# IndoorStation_PCB_M1.net
KiCad netlist of a schematic drawn in EAGLE
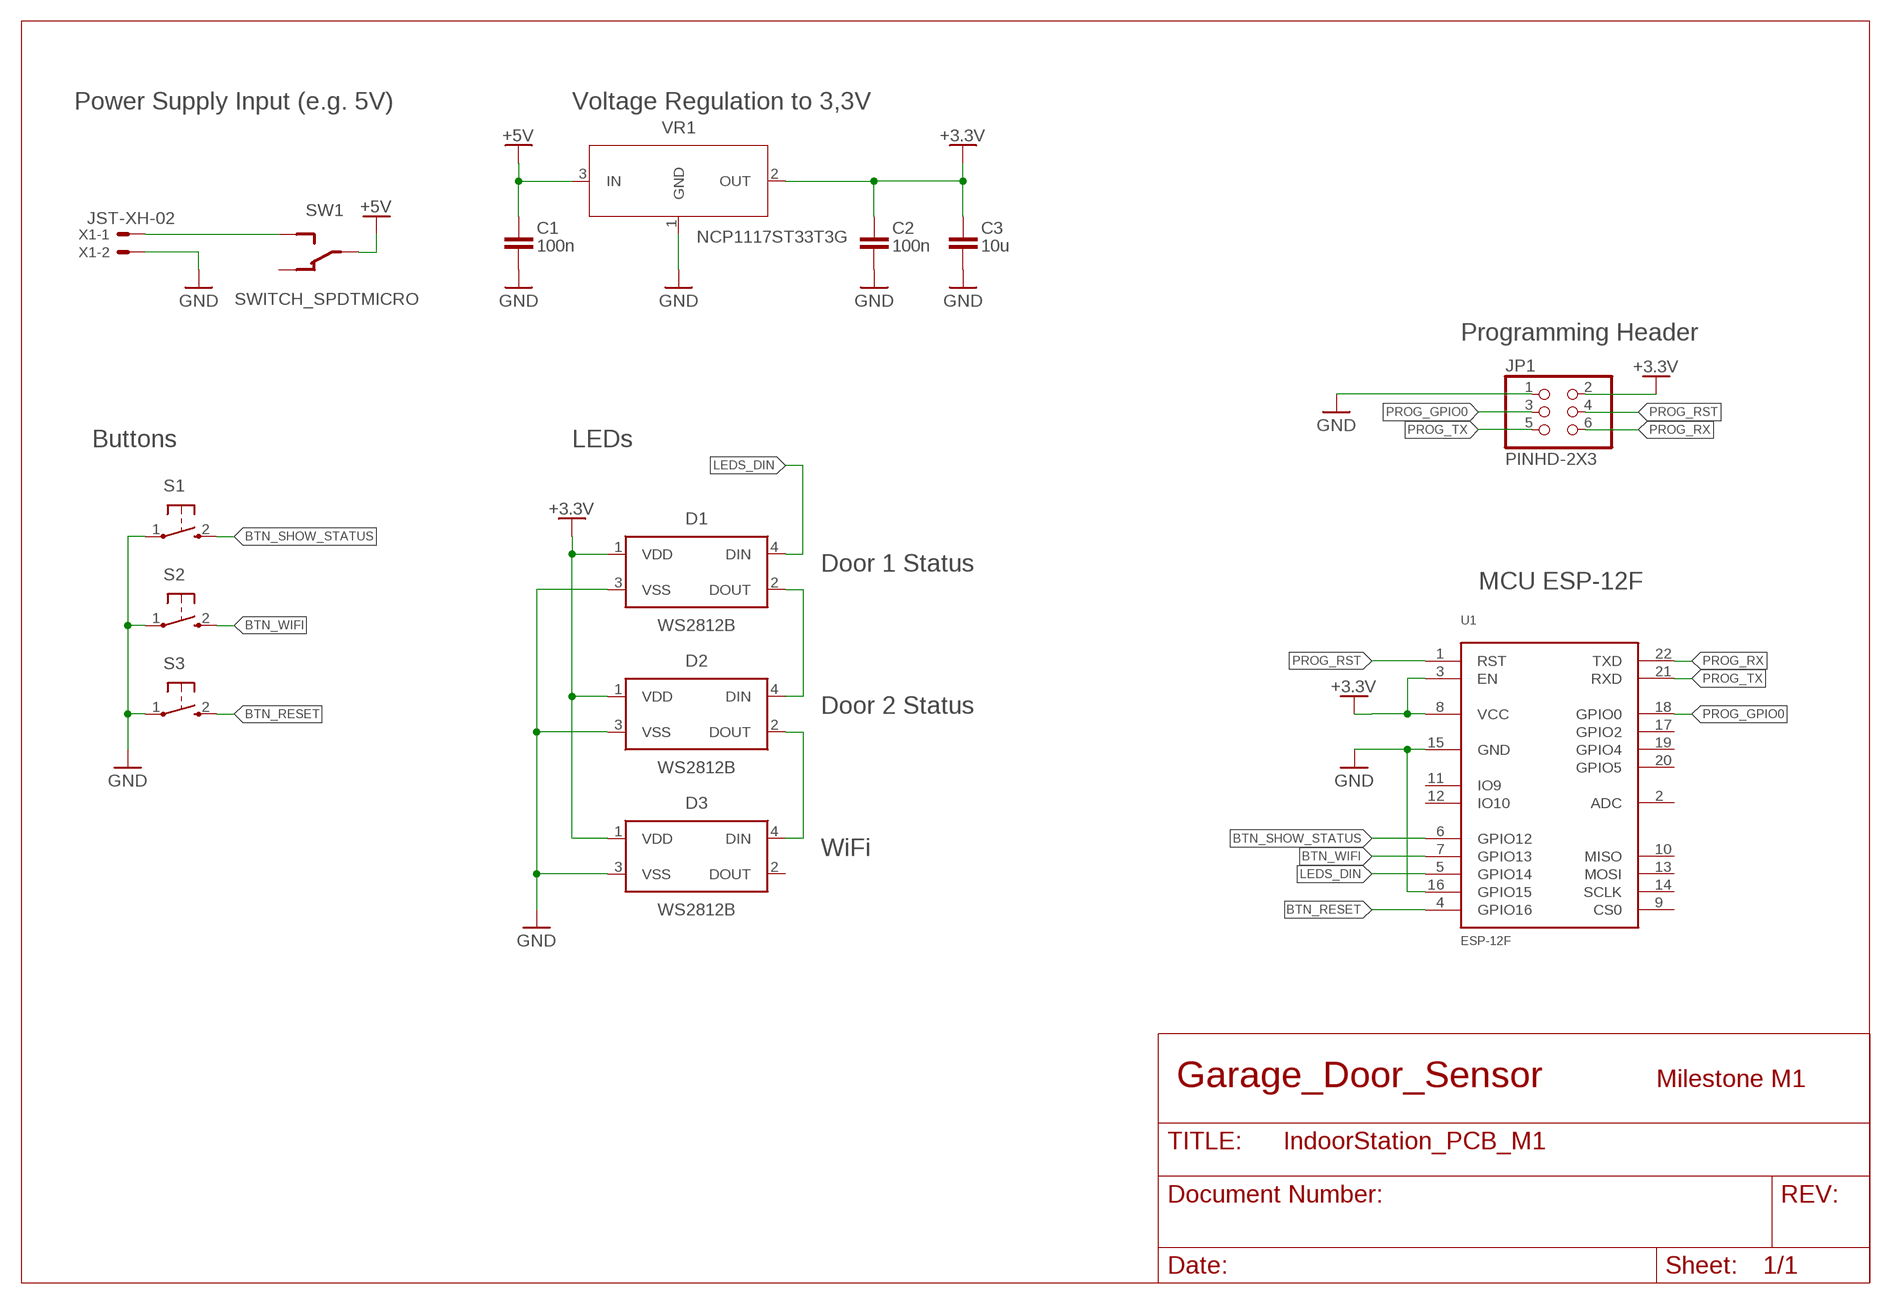
[diagram p0: schematic, sheet 1]

(export (version "E")
  (design (tool "Eeschema 10.0.6"))
  (components
    (comp (ref "C1")
      (value "100n")
      (footprint "eagle-import:CAPC2012X110")
      (libsource (lib "eagle-import") (part "CCHIP-0805(2012-METRIC)_"))
    )
    (comp (ref "C2")
      (value "100n")
      (footprint "eagle-import:CAPC2012X110")
      (libsource (lib "eagle-import") (part "CCHIP-0805(2012-METRIC)_"))
    )
    (comp (ref "C3")
      (value "10u")
      (footprint "eagle-import:CAPC2012X110")
      (libsource (lib "eagle-import") (part "CCHIP-0805(2012-METRIC)_"))
    )
    (comp (ref "D1")
      (value "WS2812B")
      (footprint "eagle-import:WS2812B")
      (fields (field (name "MANUFACTURER") "Worldsemi"))
      (libsource (lib "eagle-import") (part "WS2812B"))
    )
    (comp (ref "D2")
      (value "WS2812B")
      (footprint "eagle-import:WS2812B")
      (fields (field (name "MANUFACTURER") "Worldsemi"))
      (libsource (lib "eagle-import") (part "WS2812B"))
    )
    (comp (ref "D3")
      (value "WS2812B")
      (footprint "eagle-import:WS2812B")
      (fields (field (name "MANUFACTURER") "Worldsemi"))
      (libsource (lib "eagle-import") (part "WS2812B"))
    )
    (comp (ref "JP1")
      (value "PINHD-2X3")
      (footprint "eagle-import:2X03")
      (fields (field (name "MANUFACTURER") "Generic"))
      (libsource (lib "eagle-import") (part "PINHD-2X3"))
    )
    (comp (ref "S1")
      (value "KURZHUBTASTER")
      (footprint "eagle-import:B3F-10XX")
      (libsource (lib "eagle-import") (part "KURZHUBTASTER"))
    )
    (comp (ref "S2")
      (value "KURZHUBTASTER")
      (footprint "eagle-import:B3F-10XX")
      (libsource (lib "eagle-import") (part "KURZHUBTASTER"))
    )
    (comp (ref "S3")
      (value "KURZHUBTASTER")
      (footprint "eagle-import:B3F-10XX")
      (libsource (lib "eagle-import") (part "KURZHUBTASTER"))
    )
    (comp (ref "SW1")
      (value "SWITCH_SPDTMICRO")
      (footprint "eagle-import:MICROSWITCH_SPDT")
      (libsource (lib "eagle-import") (part "SWITCH_SPDTMICRO"))
    )
    (comp (ref "U1")
      (value "ESP-12F")
      (footprint "eagle-import:ESP-12F")
      (fields (field (name "MF") "AI-Thinker"))
      (libsource (lib "eagle-import") (part "ESP-12F"))
    )
    (comp (ref "VR1")
      (value "NCP1117ST33T3G")
      (footprint "eagle-import:SOT230P700X170-4")
      (fields (field (name "MANUFACTURER") "ON Semiconductor"))
      (libsource (lib "eagle-import") (part "NCP1117ST33T3GSOT-223"))
    )
    (comp (ref "X1")
      (value "JST-XH-02")
      (footprint "eagle-import:JST-XH-02-EDGE")
      (libsource (lib "eagle-import") (part "JST-XH-02-PIN-EDGE"))
    )
  )
  (nets
    (net (code "1") (name "+3.3V") (class "Default")
      (node (ref "C2") (pin "1") (pinfunction "1_1") (pintype "passive"))
      (node (ref "C3") (pin "1") (pinfunction "1_1") (pintype "passive"))
      (node (ref "D1") (pin "1") (pinfunction "VDD_1") (pintype "power_in"))
      (node (ref "D2") (pin "1") (pinfunction "VDD_1") (pintype "power_in"))
      (node (ref "D3") (pin "1") (pinfunction "VDD_1") (pintype "power_in"))
      (node (ref "JP1") (pin "2") (pinfunction "2_2") (pintype "passive"))
      (node (ref "U1") (pin "3") (pinfunction "EN_3") (pintype "bidirectional"))
      (node (ref "U1") (pin "8") (pinfunction "VCC_8") (pintype "bidirectional"))
      (node (ref "VR1") (pin "2") (pinfunction "OUT_2") (pintype "output"))
    )
    (net (code "2") (name "+5V") (class "Default")
      (node (ref "C1") (pin "1") (pinfunction "1_1") (pintype "passive"))
      (node (ref "SW1") (pin "P$2") (pinfunction "P$2_P$2") (pintype "passive"))
      (node (ref "VR1") (pin "3") (pinfunction "IN_3") (pintype "input"))
    )
    (net (code "3") (name "BTN_RESET") (class "Default")
      (node (ref "S3") (pin "2") (pinfunction "S_2") (pintype "passive"))
      (node (ref "U1") (pin "4") (pinfunction "GPIO16_4") (pintype "bidirectional"))
    )
    (net (code "4") (name "BTN_SHOW_STATUS") (class "Default")
      (node (ref "S1") (pin "2") (pinfunction "S_2") (pintype "passive"))
      (node (ref "U1") (pin "6") (pinfunction "GPIO12_6") (pintype "bidirectional"))
    )
    (net (code "5") (name "BTN_WIFI") (class "Default")
      (node (ref "S2") (pin "2") (pinfunction "S_2") (pintype "passive"))
      (node (ref "U1") (pin "7") (pinfunction "GPIO13_7") (pintype "bidirectional"))
    )
    (net (code "6") (name "GND") (class "Default")
      (node (ref "C1") (pin "2") (pinfunction "2_2") (pintype "passive"))
      (node (ref "C2") (pin "2") (pinfunction "2_2") (pintype "passive"))
      (node (ref "C3") (pin "2") (pinfunction "2_2") (pintype "passive"))
      (node (ref "D1") (pin "3") (pinfunction "VSS_3") (pintype "power_in"))
      (node (ref "D2") (pin "3") (pinfunction "VSS_3") (pintype "power_in"))
      (node (ref "D3") (pin "3") (pinfunction "VSS_3") (pintype "power_in"))
      (node (ref "JP1") (pin "1") (pinfunction "1_1") (pintype "passive"))
      (node (ref "S1") (pin "1") (pinfunction "P_1") (pintype "passive"))
      (node (ref "S2") (pin "1") (pinfunction "P_1") (pintype "passive"))
      (node (ref "S3") (pin "1") (pinfunction "P_1") (pintype "passive"))
      (node (ref "U1") (pin "15") (pinfunction "GND_15") (pintype "bidirectional"))
      (node (ref "U1") (pin "16") (pinfunction "GPIO15_16") (pintype "bidirectional"))
      (node (ref "VR1") (pin "1") (pinfunction "GND_1") (pintype "passive"))
      (node (ref "X1") (pin "P$2") (pinfunction "S_P$2") (pintype "passive"))
    )
    (net (code "7") (name "LEDS_DIN") (class "Default")
      (node (ref "D1") (pin "4") (pinfunction "DIN_4") (pintype "input"))
      (node (ref "U1") (pin "5") (pinfunction "GPIO14_5") (pintype "bidirectional"))
    )
    (net (code "8") (name "Net-(D1-DOUT)") (class "Default")
      (node (ref "D1") (pin "2") (pinfunction "DOUT_2") (pintype "output"))
      (node (ref "D2") (pin "4") (pinfunction "DIN_4") (pintype "input"))
    )
    (net (code "9") (name "Net-(D2-DOUT)") (class "Default")
      (node (ref "D2") (pin "2") (pinfunction "DOUT_2") (pintype "output"))
      (node (ref "D3") (pin "4") (pinfunction "DIN_4") (pintype "input"))
    )
    (net (code "10") (name "Net-(X1A-S)") (class "Default")
      (node (ref "SW1") (pin "P$1") (pinfunction "P$1_P$1") (pintype "passive"))
      (node (ref "X1") (pin "P$1") (pinfunction "S_P$1") (pintype "passive"))
    )
    (net (code "11") (name "PROG_GPIO0") (class "Default")
      (node (ref "JP1") (pin "3") (pinfunction "3_3") (pintype "passive"))
      (node (ref "U1") (pin "18") (pinfunction "GPIO0_18") (pintype "bidirectional"))
    )
    (net (code "12") (name "PROG_RST") (class "Default")
      (node (ref "JP1") (pin "4") (pinfunction "4_4") (pintype "passive"))
      (node (ref "U1") (pin "1") (pinfunction "RST_1") (pintype "bidirectional"))
    )
    (net (code "13") (name "PROG_RX") (class "Default")
      (node (ref "JP1") (pin "6") (pinfunction "6_6") (pintype "passive"))
      (node (ref "U1") (pin "22") (pinfunction "TXD_22") (pintype "bidirectional"))
    )
    (net (code "14") (name "PROG_TX") (class "Default")
      (node (ref "JP1") (pin "5") (pinfunction "5_5") (pintype "passive"))
      (node (ref "U1") (pin "21") (pinfunction "RXD_21") (pintype "bidirectional"))
    )
    (net (code "15") (name "unconnected-(D3-DOUT-Pad2)") (class "Default")
      (node (ref "D3") (pin "2") (pinfunction "DOUT_2") (pintype "output"))
    )
    (net (code "16") (name "unconnected-(SW1-PadP$3)") (class "Default")
      (node (ref "SW1") (pin "P$3") (pinfunction "P$3_P$3") (pintype "passive"))
    )
    (net (code "17") (name "unconnected-(U1-ADC-Pad2)") (class "Default")
      (node (ref "U1") (pin "2") (pinfunction "ADC_2") (pintype "bidirectional"))
    )
    (net (code "18") (name "unconnected-(U1-CS0-Pad9)") (class "Default")
      (node (ref "U1") (pin "9") (pinfunction "CS0_9") (pintype "bidirectional"))
    )
    (net (code "19") (name "unconnected-(U1-GPIO2-Pad17)") (class "Default")
      (node (ref "U1") (pin "17") (pinfunction "GPIO2_17") (pintype "bidirectional"))
    )
    (net (code "20") (name "unconnected-(U1-GPIO4-Pad19)") (class "Default")
      (node (ref "U1") (pin "19") (pinfunction "GPIO4_19") (pintype "bidirectional"))
    )
    (net (code "21") (name "unconnected-(U1-GPIO5-Pad20)") (class "Default")
      (node (ref "U1") (pin "20") (pinfunction "GPIO5_20") (pintype "bidirectional"))
    )
    (net (code "22") (name "unconnected-(U1-IO9-Pad11)") (class "Default")
      (node (ref "U1") (pin "11") (pinfunction "IO9_11") (pintype "bidirectional"))
    )
    (net (code "23") (name "unconnected-(U1-IO10-Pad12)") (class "Default")
      (node (ref "U1") (pin "12") (pinfunction "IO10_12") (pintype "bidirectional"))
    )
    (net (code "24") (name "unconnected-(U1-MISO-Pad10)") (class "Default")
      (node (ref "U1") (pin "10") (pinfunction "MISO_10") (pintype "bidirectional"))
    )
    (net (code "25") (name "unconnected-(U1-MOSI-Pad13)") (class "Default")
      (node (ref "U1") (pin "13") (pinfunction "MOSI_13") (pintype "bidirectional"))
    )
    (net (code "26") (name "unconnected-(U1-SCLK-Pad14)") (class "Default")
      (node (ref "U1") (pin "14") (pinfunction "SCLK_14") (pintype "bidirectional"))
    )
  )
)
